# 07_H3HDMI.net
KiCad netlist of a schematic drawn in Altium Designer
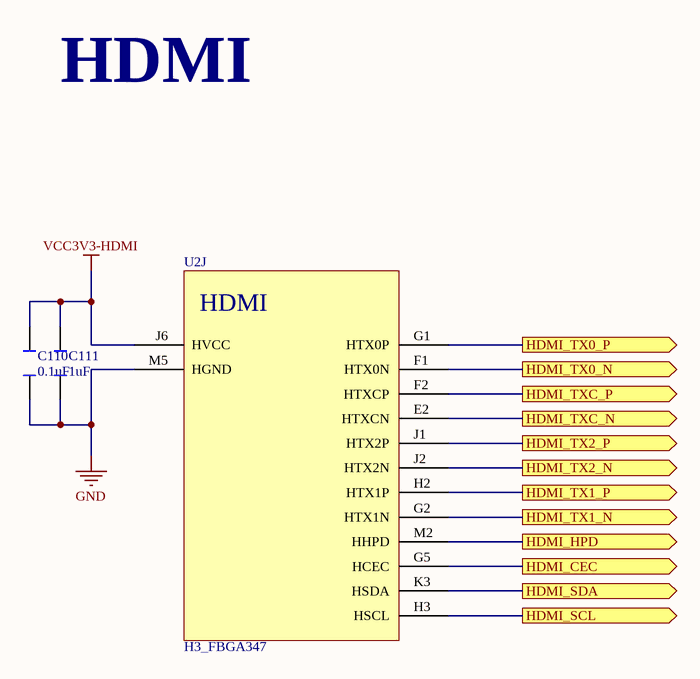
[diagram p0: 07_H3HDMI.SchDoc]

(export (version "E")
  (design (tool "Eeschema 10.0.6"))
  (components
    (comp (ref "C110") (value "0.1uF") (footprint "C0402") (libsource (lib "Board") (part "C_0.1UF")))
    (comp (ref "C111") (value "1uF") (footprint "C0402") (libsource (lib "Board") (part "C_1UF")))
    (comp (ref "U2")
      (value "H3_FBGA347")
      (footprint "H3_FBGA327")
      (libsource (lib "Board") (part "H3_FBGA347"))
    )
  )
  (nets
    (net (code "1") (name "/HDMI_CEC") (class "Default")
      (node (ref "U2") (pin "G5") (pinfunction "HCEC_G5") (pintype "passive"))
    )
    (net (code "2") (name "/HDMI_HPD") (class "Default")
      (node (ref "U2") (pin "M2") (pinfunction "HHPD_M2") (pintype "passive"))
    )
    (net (code "3") (name "/HDMI_SCL") (class "Default")
      (node (ref "U2") (pin "H3") (pinfunction "HSCL_H3") (pintype "passive"))
    )
    (net (code "4") (name "/HDMI_SDA") (class "Default")
      (node (ref "U2") (pin "K3") (pinfunction "HSDA_K3") (pintype "passive"))
    )
    (net (code "5") (name "/HDMI_TX0_N") (class "Default")
      (node (ref "U2") (pin "F1") (pinfunction "HTX0N_F1") (pintype "passive"))
    )
    (net (code "6") (name "/HDMI_TX0_P") (class "Default")
      (node (ref "U2") (pin "G1") (pinfunction "HTX0P_G1") (pintype "passive"))
    )
    (net (code "7") (name "/HDMI_TX1_N") (class "Default")
      (node (ref "U2") (pin "G2") (pinfunction "HTX1N_G2") (pintype "passive"))
    )
    (net (code "8") (name "/HDMI_TX1_P") (class "Default")
      (node (ref "U2") (pin "H2") (pinfunction "HTX1P_H2") (pintype "passive"))
    )
    (net (code "9") (name "/HDMI_TX2_N") (class "Default")
      (node (ref "U2") (pin "J2") (pinfunction "HTX2N_J2") (pintype "passive"))
    )
    (net (code "10") (name "/HDMI_TX2_P") (class "Default")
      (node (ref "U2") (pin "J1") (pinfunction "HTX2P_J1") (pintype "passive"))
    )
    (net (code "11") (name "/HDMI_TXC_N") (class "Default")
      (node (ref "U2") (pin "E2") (pinfunction "HTXCN_E2") (pintype "passive"))
    )
    (net (code "12") (name "/HDMI_TXC_P") (class "Default")
      (node (ref "U2") (pin "F2") (pinfunction "HTXCP_F2") (pintype "passive"))
    )
    (net (code "13") (name "GND") (class "Default")
      (node (ref "C110") (pin "1") (pinfunction "17_1") (pintype "passive"))
      (node (ref "C111") (pin "1") (pinfunction "17_1") (pintype "passive"))
      (node (ref "U2") (pin "M5") (pinfunction "HGND_M5") (pintype "passive"))
    )
    (net (code "14") (name "VCC3V3-HDMI") (class "Default")
      (node (ref "C110") (pin "2") (pinfunction "18_2") (pintype "passive"))
      (node (ref "C111") (pin "2") (pinfunction "18_2") (pintype "passive"))
      (node (ref "U2") (pin "J6") (pinfunction "HVCC_J6") (pintype "passive"))
    )
  )
)
